# cpu_board.net
KiCad netlist of a schematic drawn in Altium Designer
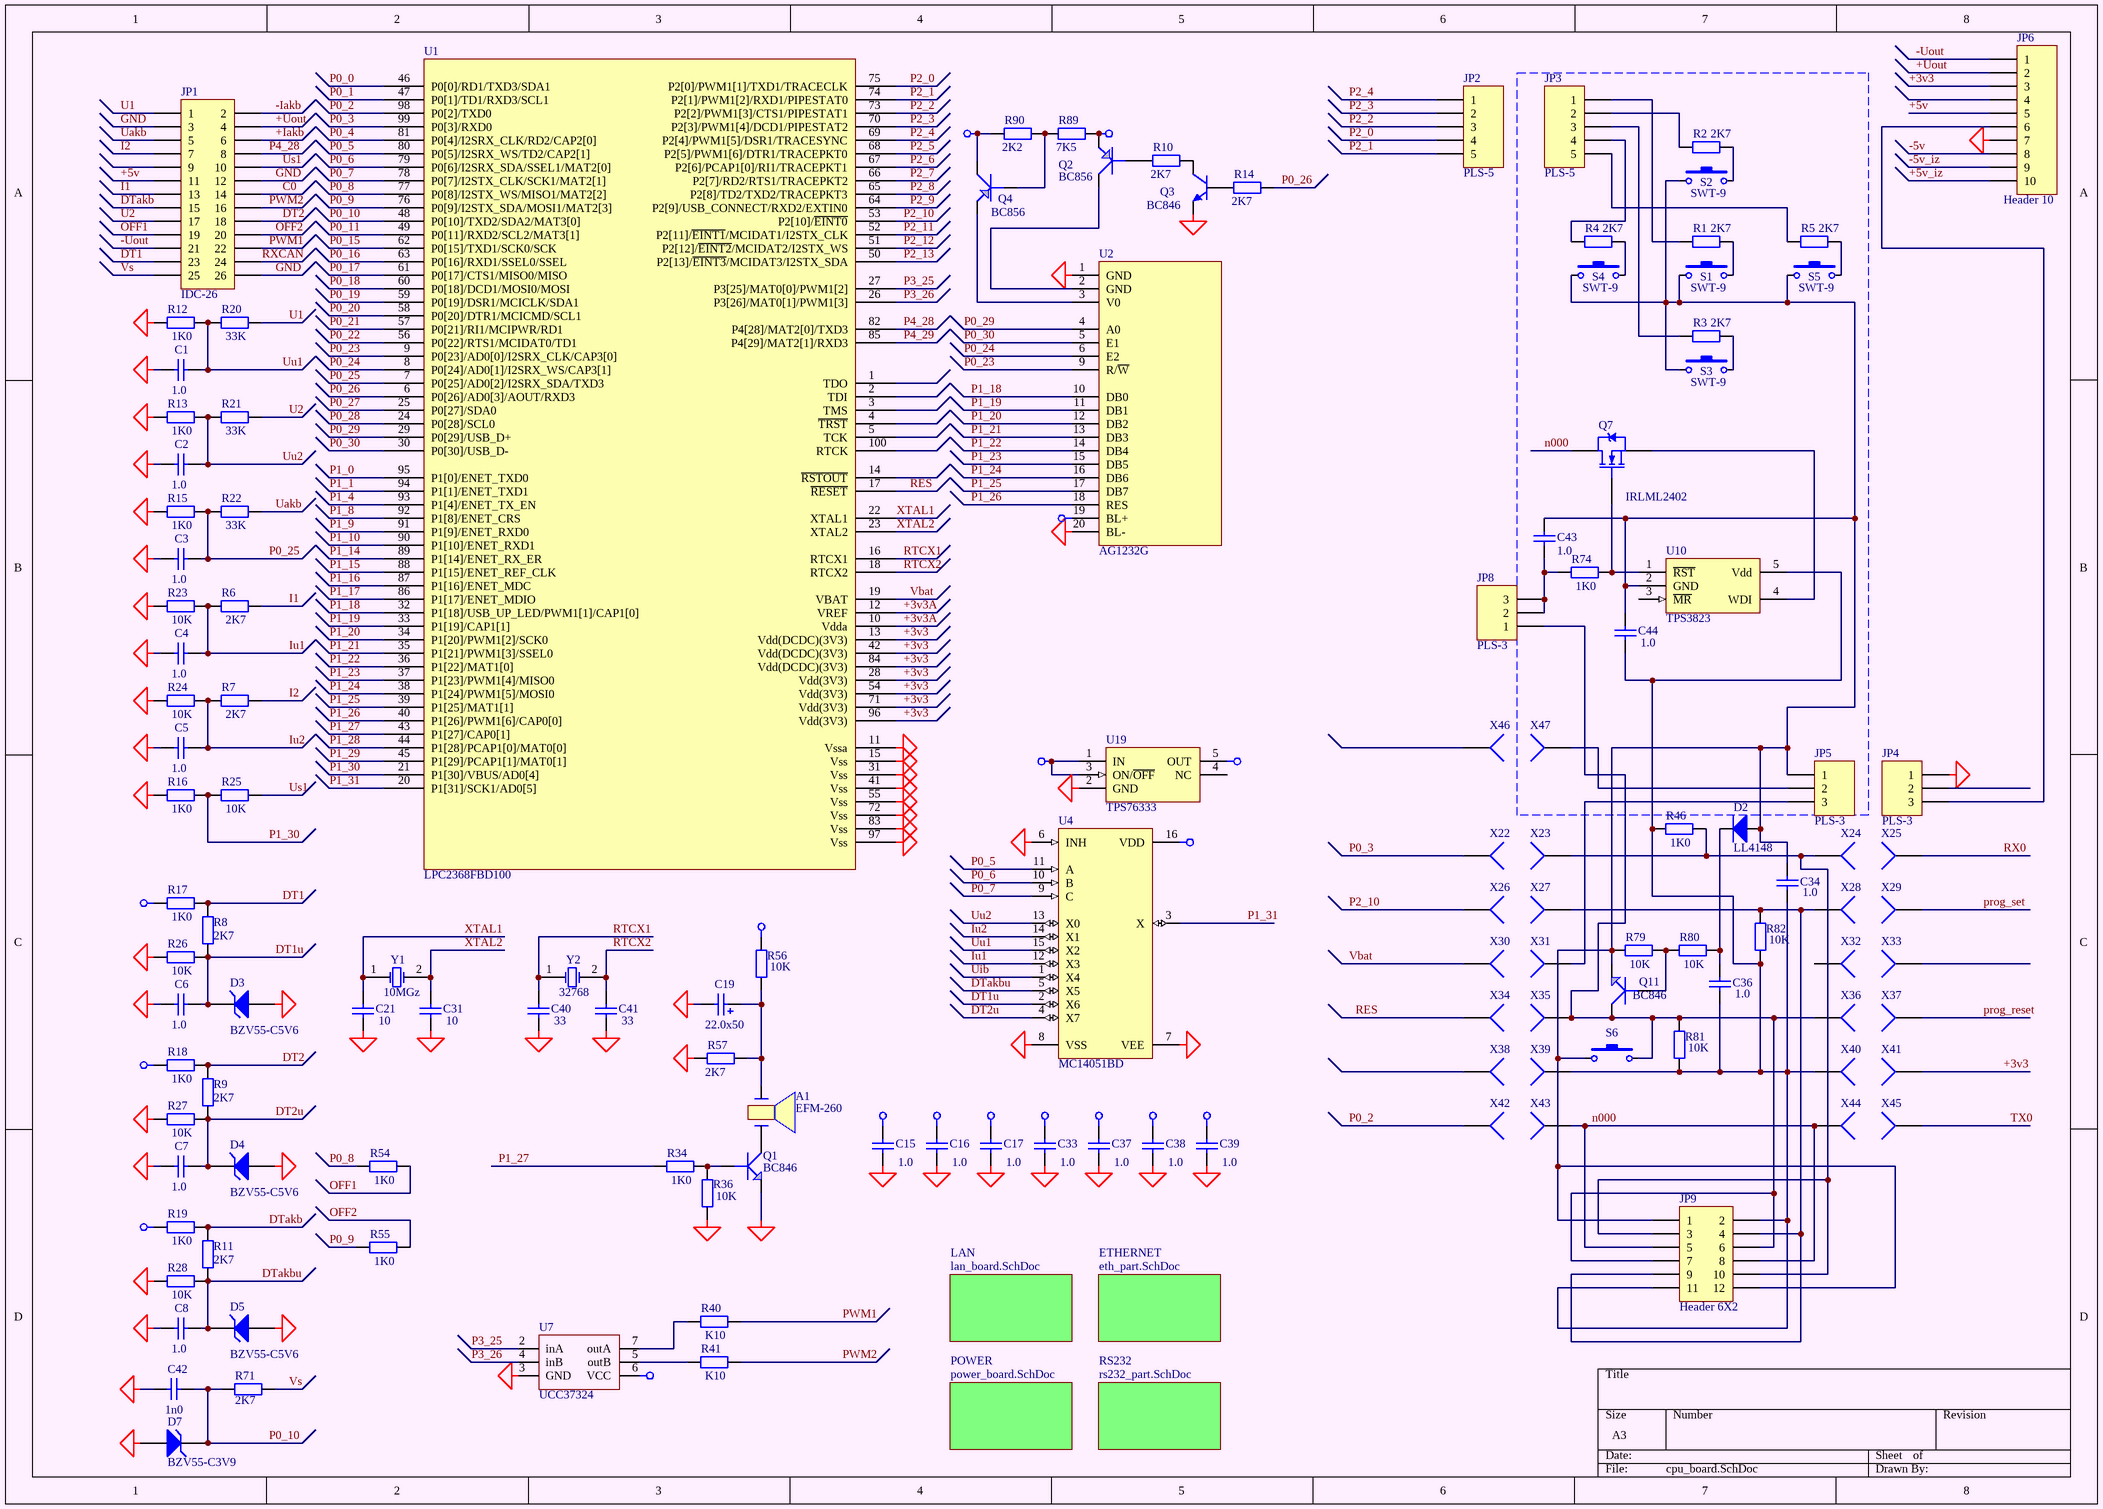
[diagram p0: cpu_board.SchDoc]

(export (version "E")
  (design (tool "Eeschema 10.0.6"))
  (components
    (comp (ref "A1") (value "EFM-260") (footprint "Pjezo15") (libsource (lib "PAL") (part "PJEZ0")))
    (comp (ref "C1")
      (value "1.0")
      (footprint "C3216-1206")
      (description "Capacitor (Semiconductor SIM Model)")
      (fields (field (name "MANUFACTURER") "Generic Components") (field (name "PUBLISHER") "Altium Limited"))
      (libsource (lib "Miscellaneous Devices") (part "Cap Semi"))
    )
    (comp (ref "C2")
      (value "1.0")
      (footprint "C3216-1206")
      (description "Capacitor (Semiconductor SIM Model)")
      (fields (field (name "MANUFACTURER") "Generic Components") (field (name "PUBLISHER") "Altium Limited"))
      (libsource (lib "Miscellaneous Devices") (part "Cap Semi"))
    )
    (comp (ref "C3")
      (value "1.0")
      (footprint "C3216-1206")
      (description "Capacitor (Semiconductor SIM Model)")
      (fields (field (name "MANUFACTURER") "Generic Components") (field (name "PUBLISHER") "Altium Limited"))
      (libsource (lib "Miscellaneous Devices") (part "Cap Semi"))
    )
    (comp (ref "C4")
      (value "1.0")
      (footprint "C3216-1206")
      (description "Capacitor (Semiconductor SIM Model)")
      (fields (field (name "MANUFACTURER") "Generic Components") (field (name "PUBLISHER") "Altium Limited"))
      (libsource (lib "Miscellaneous Devices") (part "Cap Semi"))
    )
    (comp (ref "C5")
      (value "1.0")
      (footprint "C3216-1206")
      (description "Capacitor (Semiconductor SIM Model)")
      (fields (field (name "MANUFACTURER") "Generic Components") (field (name "PUBLISHER") "Altium Limited"))
      (libsource (lib "Miscellaneous Devices") (part "Cap Semi"))
    )
    (comp (ref "C6")
      (value "1.0")
      (footprint "C3216-1206")
      (description "Capacitor (Semiconductor SIM Model)")
      (fields (field (name "MANUFACTURER") "Generic Components") (field (name "PUBLISHER") "Altium Limited"))
      (libsource (lib "Miscellaneous Devices") (part "Cap Semi"))
    )
    (comp (ref "C7")
      (value "1.0")
      (footprint "C3216-1206")
      (description "Capacitor (Semiconductor SIM Model)")
      (fields (field (name "MANUFACTURER") "Generic Components") (field (name "PUBLISHER") "Altium Limited"))
      (libsource (lib "Miscellaneous Devices") (part "Cap Semi"))
    )
    (comp (ref "C8")
      (value "1.0")
      (footprint "_1206")
      (description "Capacitor (Semiconductor SIM Model)")
      (fields (field (name "MANUFACTURER") "Generic Components") (field (name "PUBLISHER") "Altium Limited"))
      (libsource (lib "Miscellaneous Devices") (part "Cap Semi"))
    )
    (comp (ref "C15")
      (value "1.0")
      (footprint "C3216-1206")
      (description "Capacitor (Semiconductor SIM Model)")
      (fields (field (name "MANUFACTURER") "Generic Components") (field (name "PUBLISHER") "Altium Limited"))
      (libsource (lib "Miscellaneous Devices") (part "Cap Semi"))
    )
    (comp (ref "C16")
      (value "1.0")
      (footprint "C3216-1206")
      (description "Capacitor (Semiconductor SIM Model)")
      (fields (field (name "MANUFACTURER") "Generic Components") (field (name "PUBLISHER") "Altium Limited"))
      (libsource (lib "Miscellaneous Devices") (part "Cap Semi"))
    )
    (comp (ref "C17")
      (value "1.0")
      (footprint "_1206")
      (description "Capacitor (Semiconductor SIM Model)")
      (fields (field (name "MANUFACTURER") "Generic Components") (field (name "PUBLISHER") "Altium Limited"))
      (libsource (lib "Miscellaneous Devices") (part "Cap Semi"))
    )
    (comp (ref "C19")
      (value "22.0x50")
      (footprint "el3")
      (description "Polarized Capacitor (Radial)")
      (fields (field (name "MANUFACTURER") "Generic Components") (field (name "PUBLISHER") "Altium Limited"))
      (libsource (lib "PAL") (part "Cap Pol1"))
    )
    (comp (ref "C21")
      (value "10")
      (footprint "_1206")
      (description "Capacitor (Semiconductor SIM Model)")
      (fields (field (name "MANUFACTURER") "Generic Components") (field (name "PUBLISHER") "Altium Limited"))
      (libsource (lib "Miscellaneous Devices") (part "Cap Semi"))
    )
    (comp (ref "C31")
      (value "10")
      (footprint "_1206")
      (description "Capacitor (Semiconductor SIM Model)")
      (fields (field (name "MANUFACTURER") "Generic Components") (field (name "PUBLISHER") "Altium Limited"))
      (libsource (lib "Miscellaneous Devices") (part "Cap Semi"))
    )
    (comp (ref "C33")
      (value "1.0")
      (footprint "_1206")
      (description "Capacitor (Semiconductor SIM Model)")
      (fields (field (name "MANUFACTURER") "Generic Components") (field (name "PUBLISHER") "Altium Limited"))
      (libsource (lib "Miscellaneous Devices") (part "Cap Semi"))
    )
    (comp (ref "C34")
      (value "1.0")
      (footprint "C3216-1206")
      (description "Capacitor (Semiconductor SIM Model)")
      (fields (field (name "MANUFACTURER") "Generic Components") (field (name "PUBLISHER") "Altium Limited"))
      (libsource (lib "Miscellaneous Devices") (part "Cap Semi"))
    )
    (comp (ref "C36")
      (value "1.0")
      (footprint "C3216-1206")
      (description "Capacitor (Semiconductor SIM Model)")
      (fields (field (name "MANUFACTURER") "Generic Components") (field (name "PUBLISHER") "Altium Limited"))
      (libsource (lib "Miscellaneous Devices") (part "Cap Semi"))
    )
    (comp (ref "C37")
      (value "1.0")
      (footprint "_1206")
      (description "Capacitor (Semiconductor SIM Model)")
      (fields (field (name "MANUFACTURER") "Generic Components") (field (name "PUBLISHER") "Altium Limited"))
      (libsource (lib "Miscellaneous Devices") (part "Cap Semi"))
    )
    (comp (ref "C38")
      (value "1.0")
      (footprint "_1206")
      (description "Capacitor (Semiconductor SIM Model)")
      (fields (field (name "MANUFACTURER") "Generic Components") (field (name "PUBLISHER") "Altium Limited"))
      (libsource (lib "Miscellaneous Devices") (part "Cap Semi"))
    )
    (comp (ref "C39")
      (value "1.0")
      (footprint "_1206")
      (description "Capacitor (Semiconductor SIM Model)")
      (fields (field (name "MANUFACTURER") "Generic Components") (field (name "PUBLISHER") "Altium Limited"))
      (libsource (lib "Miscellaneous Devices") (part "Cap Semi"))
    )
    (comp (ref "C40")
      (value "33")
      (footprint "_1206")
      (description "Capacitor (Semiconductor SIM Model)")
      (fields (field (name "MANUFACTURER") "Generic Components") (field (name "PUBLISHER") "Altium Limited"))
      (libsource (lib "Miscellaneous Devices") (part "Cap Semi"))
    )
    (comp (ref "C41")
      (value "33")
      (footprint "_1206")
      (description "Capacitor (Semiconductor SIM Model)")
      (fields (field (name "MANUFACTURER") "Generic Components") (field (name "PUBLISHER") "Altium Limited"))
      (libsource (lib "Miscellaneous Devices") (part "Cap Semi"))
    )
    (comp (ref "C42")
      (value "1n0")
      (footprint "_1206")
      (description "Capacitor (Semiconductor SIM Model)")
      (fields (field (name "MANUFACTURER") "Generic Components") (field (name "PUBLISHER") "Altium Limited"))
      (libsource (lib "Miscellaneous Devices") (part "Cap Semi"))
    )
    (comp (ref "C43")
      (value "1.0")
      (footprint "_1206")
      (description "Capacitor")
      (fields (field (name "MANUFACTURER") "Generic Components") (field (name "PUBLISHER") "Altium Limited"))
      (libsource (lib "Miscellaneous Devices") (part "Cap Semi"))
    )
    (comp (ref "C44")
      (value "1.0")
      (footprint "_1206")
      (description "Capacitor")
      (fields (field (name "MANUFACTURER") "Generic Components") (field (name "PUBLISHER") "Altium Limited"))
      (libsource (lib "Miscellaneous Devices") (part "Cap Semi"))
    )
    (comp (ref "D2")
      (value "LL4148")
      (footprint "_1206d")
      (description "Default Diode")
      (fields (field (name "MANUFACTURER") "Generic Components") (field (name "PUBLISHER") "Altium Limited"))
      (libsource (lib "PAL") (part "Diode"))
    )
    (comp (ref "D3")
      (value "BZV55-C5V6")
      (footprint "_1206d")
      (description "Zener Diode")
      (fields (field (name "MANUFACTURER") "Generic Components") (field (name "PUBLISHER") "Altium Limited"))
      (libsource (lib "Miscellaneous Devices") (part "D Zener"))
    )
    (comp (ref "D4")
      (value "BZV55-C5V6")
      (footprint "_1206d")
      (description "Zener Diode")
      (fields (field (name "MANUFACTURER") "Generic Components") (field (name "PUBLISHER") "Altium Limited"))
      (libsource (lib "Miscellaneous Devices") (part "D Zener"))
    )
    (comp (ref "D5")
      (value "BZV55-C5V6")
      (footprint "_1206d")
      (description "Zener Diode")
      (fields (field (name "MANUFACTURER") "Generic Components") (field (name "PUBLISHER") "Altium Limited"))
      (libsource (lib "Miscellaneous Devices") (part "D Zener"))
    )
    (comp (ref "D7")
      (value "BZV55-C3V9")
      (footprint "_1206d")
      (description "Zener Diode")
      (fields (field (name "MANUFACTURER") "Generic Components") (field (name "PUBLISHER") "Altium Limited"))
      (libsource (lib "Miscellaneous Devices") (part "D Zener"))
    )
    (comp (ref "JP1")
      (value "IDC-26")
      (footprint "SCM-26")
      (description "Header, 13-Pin, Dual row")
      (fields (field (name "MANUFACTURER") "Generic Components") (field (name "PUBLISHER") "Altium Limited"))
      (libsource (lib "Miscellaneous Connectors") (part "MHDR2X13"))
    )
    (comp (ref "JP2")
      (value "PLS-5")
      (footprint "HDR1X5")
      (description "Header, 5-Pin")
      (fields (field (name "MANUFACTURER") "Generic Components") (field (name "PUBLISHER") "Altium Limited"))
      (libsource (lib "Miscellaneous Connectors") (part "Header 5"))
    )
    (comp (ref "JP3")
      (value "PLS-5")
      (footprint "HDR1X5")
      (description "Header, 5-Pin")
      (fields (field (name "MANUFACTURER") "Generic Components") (field (name "PUBLISHER") "Altium Limited"))
      (libsource (lib "") (part "Header 5_1"))
    )
    (comp (ref "JP4")
      (value "PLS-3")
      (footprint "HDR1X3")
      (description "Header, 3-Pin")
      (fields (field (name "MANUFACTURER") "Generic Components") (field (name "PUBLISHER") "Altium Limited"))
      (libsource (lib "Miscellaneous Connectors") (part "Header 3"))
    )
    (comp (ref "JP5")
      (value "PLS-3")
      (footprint "HDR1X3")
      (description "Header, 3-Pin")
      (fields (field (name "MANUFACTURER") "Generic Components") (field (name "PUBLISHER") "Altium Limited"))
      (libsource (lib "") (part "Header 3_2"))
    )
    (comp (ref "JP6")
      (value "Header 10")
      (footprint "HDR2X5")
      (description "Header, 10-Pin")
      (fields (field (name "MANUFACTURER") "Generic Components") (field (name "PUBLISHER") "Altium Limited"))
      (libsource (lib "Miscellaneous Connectors") (part "Header 10"))
    )
    (comp (ref "JP8")
      (value "PLS-3")
      (footprint "HDR1X3")
      (description "Header, 3-Pin")
      (fields (field (name "MANUFACTURER") "Generic Components") (field (name "PUBLISHER") "Altium Limited"))
      (libsource (lib "") (part "Header 3_1"))
    )
    (comp (ref "JP9")
      (value "Header 6X2")
      (footprint "sl-12mini")
      (description "Header, 6-Pin, Dual row")
      (fields (field (name "MANUFACTURER") "Generic Components") (field (name "PUBLISHER") "Altium Limited"))
      (libsource (lib "Miscellaneous Connectors") (part "Header 6X2"))
    )
    (comp (ref "Q1") (value "BC846") (footprint "SOT 23:SO-G3") (libsource (lib "MAIN") (part "GT122")))
    (comp (ref "Q2") (value "BC856") (footprint "SO-G3") (libsource (lib "MAIN") (part "GT109")))
    (comp (ref "Q3")
      (value "BC846")
      (footprint "SO-G3")
      (description "General Purpose Transistor NPN Silicon")
      (fields (field (name "MANUFACTURER") "Motorola") (field (name "PUBLISHER") "Altium Limited"))
      (libsource (lib "PAL") (part "BC847ALT1"))
    )
    (comp (ref "Q4") (value "BC856") (footprint "SO-G3") (libsource (lib "MAIN") (part "GT109")))
    (comp (ref "Q7")
      (value "IRLML2402")
      (footprint "SO-G3")
      (description "HEXFET Power MOSFET")
      (fields
        (field (name "MANUFACTURER") "International Rectifier")
        (field (name "ALTIUM_VALUE") "IRLML2402")
        (field (name "PUBLISHER") "Altium Limited")
      )
      (libsource (lib "IR Discrete MOSFET") (part "IRLML2402"))
    )
    (comp (ref "Q11") (value "BC846") (footprint "SOT 23:SO-G3") (libsource (lib "MAIN") (part "GT122")))
    (comp (ref "R1")
      (value "2K7")
      (footprint "_1206")
      (description "Resistor")
      (fields (field (name "MANUFACTURER") "Generic Components") (field (name "PUBLISHER") "Altium Limited"))
      (libsource (lib "Miscellaneous Devices") (part "Res2"))
    )
    (comp (ref "R2")
      (value "2K7")
      (footprint "_1206")
      (description "Resistor")
      (fields (field (name "MANUFACTURER") "Generic Components") (field (name "PUBLISHER") "Altium Limited"))
      (libsource (lib "Miscellaneous Devices") (part "Res2"))
    )
    (comp (ref "R3")
      (value "2K7")
      (footprint "_1206")
      (description "Resistor")
      (fields (field (name "MANUFACTURER") "Generic Components") (field (name "PUBLISHER") "Altium Limited"))
      (libsource (lib "Miscellaneous Devices") (part "Res2"))
    )
    (comp (ref "R4")
      (value "2K7")
      (footprint "_1206")
      (description "Resistor")
      (fields (field (name "MANUFACTURER") "Generic Components") (field (name "PUBLISHER") "Altium Limited"))
      (libsource (lib "Miscellaneous Devices") (part "Res2"))
    )
    (comp (ref "R5")
      (value "2K7")
      (footprint "_1206")
      (description "Resistor")
      (fields (field (name "MANUFACTURER") "Generic Components") (field (name "PUBLISHER") "Altium Limited"))
      (libsource (lib "Miscellaneous Devices") (part "Res2"))
    )
    (comp (ref "R6")
      (value "2K7")
      (footprint "_1206")
      (description "Resistor")
      (fields (field (name "MANUFACTURER") "Generic Components") (field (name "PUBLISHER") "Altium Limited"))
      (libsource (lib "") (part "Res2_2"))
    )
    (comp (ref "R7")
      (value "2K7")
      (footprint "_1206")
      (description "Resistor")
      (fields (field (name "MANUFACTURER") "Generic Components") (field (name "PUBLISHER") "Altium Limited"))
      (libsource (lib "") (part "Res2_2"))
    )
    (comp (ref "R8")
      (value "2K7")
      (footprint "_1206")
      (description "Resistor")
      (fields (field (name "MANUFACTURER") "Generic Components") (field (name "PUBLISHER") "Altium Limited"))
      (libsource (lib "") (part "Res2_3"))
    )
    (comp (ref "R9")
      (value "2K7")
      (footprint "_1206")
      (description "Resistor")
      (fields (field (name "MANUFACTURER") "Generic Components") (field (name "PUBLISHER") "Altium Limited"))
      (libsource (lib "") (part "Res2_3"))
    )
    (comp (ref "R10")
      (value "2K7")
      (footprint "_1206")
      (description "Resistor")
      (fields (field (name "MANUFACTURER") "Generic Components") (field (name "PUBLISHER") "Altium Limited"))
      (libsource (lib "") (part "Res2_1"))
    )
    (comp (ref "R11")
      (value "2K7")
      (footprint "_1206")
      (description "Resistor")
      (fields (field (name "MANUFACTURER") "Generic Components") (field (name "PUBLISHER") "Altium Limited"))
      (libsource (lib "") (part "Res2_3"))
    )
    (comp (ref "R12")
      (value "1K0")
      (footprint "_1206")
      (description "Resistor")
      (fields (field (name "MANUFACTURER") "Generic Components") (field (name "PUBLISHER") "Altium Limited"))
      (libsource (lib "") (part "Res2_1"))
    )
    (comp (ref "R13")
      (value "1K0")
      (footprint "_1206")
      (description "Resistor")
      (fields (field (name "MANUFACTURER") "Generic Components") (field (name "PUBLISHER") "Altium Limited"))
      (libsource (lib "") (part "Res2_1"))
    )
    (comp (ref "R14")
      (value "2K7")
      (footprint "_1206")
      (description "Resistor")
      (fields (field (name "MANUFACTURER") "Generic Components") (field (name "PUBLISHER") "Altium Limited"))
      (libsource (lib "") (part "Res2_1"))
    )
    (comp (ref "R15")
      (value "1K0")
      (footprint "_1206")
      (description "Resistor")
      (fields (field (name "MANUFACTURER") "Generic Components") (field (name "PUBLISHER") "Altium Limited"))
      (libsource (lib "") (part "Res2_1"))
    )
    (comp (ref "R16")
      (value "1K0")
      (footprint "_1206")
      (description "Resistor")
      (fields (field (name "MANUFACTURER") "Generic Components") (field (name "PUBLISHER") "Altium Limited"))
      (libsource (lib "") (part "Res2_1"))
    )
    (comp (ref "R17")
      (value "1K0")
      (footprint "_1206")
      (description "Resistor")
      (fields (field (name "MANUFACTURER") "Generic Components") (field (name "PUBLISHER") "Altium Limited"))
      (libsource (lib "") (part "Res2_1"))
    )
    (comp (ref "R18")
      (value "1K0")
      (footprint "_1206")
      (description "Resistor")
      (fields (field (name "MANUFACTURER") "Generic Components") (field (name "PUBLISHER") "Altium Limited"))
      (libsource (lib "") (part "Res2_1"))
    )
    (comp (ref "R19")
      (value "1K0")
      (footprint "_1206")
      (description "Resistor")
      (fields (field (name "MANUFACTURER") "Generic Components") (field (name "PUBLISHER") "Altium Limited"))
      (libsource (lib "") (part "Res2_1"))
    )
    (comp (ref "R20")
      (value "33K")
      (footprint "_1206")
      (description "Resistor")
      (fields (field (name "MANUFACTURER") "Generic Components") (field (name "PUBLISHER") "Altium Limited"))
      (libsource (lib "") (part "Res2_2"))
    )
    (comp (ref "R21")
      (value "33K")
      (footprint "_1206")
      (description "Resistor")
      (fields (field (name "MANUFACTURER") "Generic Components") (field (name "PUBLISHER") "Altium Limited"))
      (libsource (lib "") (part "Res2_2"))
    )
    (comp (ref "R22")
      (value "33K")
      (footprint "_1206")
      (description "Resistor")
      (fields (field (name "MANUFACTURER") "Generic Components") (field (name "PUBLISHER") "Altium Limited"))
      (libsource (lib "") (part "Res2_2"))
    )
    (comp (ref "R23")
      (value "10K")
      (footprint "_1206")
      (description "Resistor")
      (fields (field (name "MANUFACTURER") "Generic Components") (field (name "PUBLISHER") "Altium Limited"))
      (libsource (lib "") (part "Res2_2"))
    )
    (comp (ref "R24")
      (value "10K")
      (footprint "_1206")
      (description "Resistor")
      (fields (field (name "MANUFACTURER") "Generic Components") (field (name "PUBLISHER") "Altium Limited"))
      (libsource (lib "") (part "Res2_2"))
    )
    (comp (ref "R25")
      (value "10K")
      (footprint "_1206")
      (description "Resistor")
      (fields (field (name "MANUFACTURER") "Generic Components") (field (name "PUBLISHER") "Altium Limited"))
      (libsource (lib "") (part "Res2_2"))
    )
    (comp (ref "R26")
      (value "10K")
      (footprint "_1206")
      (description "Resistor")
      (fields (field (name "MANUFACTURER") "Generic Components") (field (name "PUBLISHER") "Altium Limited"))
      (libsource (lib "") (part "Res2_2"))
    )
    (comp (ref "R27")
      (value "10K")
      (footprint "_1206")
      (description "Resistor")
      (fields (field (name "MANUFACTURER") "Generic Components") (field (name "PUBLISHER") "Altium Limited"))
      (libsource (lib "") (part "Res2_2"))
    )
    (comp (ref "R28")
      (value "10K")
      (footprint "_1206")
      (description "Resistor")
      (fields (field (name "MANUFACTURER") "Generic Components") (field (name "PUBLISHER") "Altium Limited"))
      (libsource (lib "") (part "Res2_2"))
    )
    (comp (ref "R34")
      (value "1K0")
      (footprint "_1206")
      (description "Resistor")
      (fields (field (name "MANUFACTURER") "Generic Components") (field (name "PUBLISHER") "Altium Limited"))
      (libsource (lib "") (part "Res2_2"))
    )
    (comp (ref "R36")
      (value "10K")
      (footprint "_1206")
      (description "Resistor")
      (fields (field (name "MANUFACTURER") "Generic Components") (field (name "PUBLISHER") "Altium Limited"))
      (libsource (lib "") (part "Res2_3"))
    )
    (comp (ref "R40")
      (value "K10")
      (footprint "_1206")
      (description "Resistor")
      (fields (field (name "MANUFACTURER") "Generic Components") (field (name "PUBLISHER") "Altium Limited"))
      (libsource (lib "") (part "Res2_1"))
    )
    (comp (ref "R41")
      (value "K10")
      (footprint "_1206")
      (description "Resistor")
      (fields (field (name "MANUFACTURER") "Generic Components") (field (name "PUBLISHER") "Altium Limited"))
      (libsource (lib "") (part "Res2_1"))
    )
    (comp (ref "R46")
      (value "1K0")
      (footprint "_1206")
      (description "Resistor")
      (fields (field (name "MANUFACTURER") "Generic Components") (field (name "PUBLISHER") "Altium Limited"))
      (libsource (lib "") (part "Res2_1"))
    )
    (comp (ref "R54")
      (value "1K0")
      (footprint "_1206")
      (description "Resistor")
      (fields (field (name "MANUFACTURER") "Generic Components") (field (name "PUBLISHER") "Altium Limited"))
      (libsource (lib "") (part "Res2_2"))
    )
    (comp (ref "R55")
      (value "1K0")
      (footprint "_1206")
      (description "Resistor")
      (fields (field (name "MANUFACTURER") "Generic Components") (field (name "PUBLISHER") "Altium Limited"))
      (libsource (lib "") (part "Res2_2"))
    )
    (comp (ref "R56")
      (value "10K")
      (footprint "_1206")
      (description "Resistor")
      (fields (field (name "MANUFACTURER") "Generic Components") (field (name "PUBLISHER") "Altium Limited"))
      (libsource (lib "") (part "Res2_3"))
    )
    (comp (ref "R57")
      (value "2K7")
      (footprint "_1206")
      (description "Resistor")
      (fields (field (name "MANUFACTURER") "Generic Components") (field (name "PUBLISHER") "Altium Limited"))
      (libsource (lib "") (part "Res2_2"))
    )
    (comp (ref "R71")
      (value "2K7")
      (footprint "_1206")
      (description "Resistor")
      (fields (field (name "MANUFACTURER") "Generic Components") (field (name "PUBLISHER") "Altium Limited"))
      (libsource (lib "") (part "Res2_1"))
    )
    (comp (ref "R74")
      (value "1K0")
      (footprint "_1206")
      (description "Resistor")
      (fields (field (name "MANUFACTURER") "Generic Components") (field (name "PUBLISHER") "Altium Limited"))
      (libsource (lib "") (part "Res2_1"))
    )
    (comp (ref "R79")
      (value "10K")
      (footprint "_1206")
      (description "Resistor")
      (fields (field (name "MANUFACTURER") "Generic Components") (field (name "PUBLISHER") "Altium Limited"))
      (libsource (lib "") (part "Res2_2"))
    )
    (comp (ref "R80")
      (value "10K")
      (footprint "_1206")
      (description "Resistor")
      (fields (field (name "MANUFACTURER") "Generic Components") (field (name "PUBLISHER") "Altium Limited"))
      (libsource (lib "") (part "Res2_2"))
    )
    (comp (ref "R81")
      (value "10K")
      (footprint "_1206")
      (description "Resistor")
      (fields (field (name "MANUFACTURER") "Generic Components") (field (name "PUBLISHER") "Altium Limited"))
      (libsource (lib "") (part "Res2_3"))
    )
    (comp (ref "R82")
      (value "10K")
      (footprint "_1206")
      (description "Resistor")
      (fields (field (name "MANUFACTURER") "Generic Components") (field (name "PUBLISHER") "Altium Limited"))
      (libsource (lib "") (part "Res2_3"))
    )
    (comp (ref "R89")
      (value "7K5")
      (footprint "_1206")
      (description "Resistor")
      (fields (field (name "MANUFACTURER") "Generic Components") (field (name "PUBLISHER") "Altium Limited"))
      (libsource (lib "") (part "Res2_2"))
    )
    (comp (ref "R90")
      (value "2K2")
      (footprint "_1206")
      (description "Resistor")
      (fields (field (name "MANUFACTURER") "Generic Components") (field (name "PUBLISHER") "Altium Limited"))
      (libsource (lib "") (part "Res2_2"))
    )
    (comp (ref "S1")
      (value "SWT-9")
      (footprint "SWT-9")
      (description "Switch")
      (fields (field (name "MANUFACTURER") "Generic Components") (field (name "PUBLISHER") "Altium Limited"))
      (libsource (lib "PAL") (part "SWT-9"))
    )
    (comp (ref "S2")
      (value "SWT-9")
      (footprint "SWT-9")
      (description "Switch")
      (fields (field (name "MANUFACTURER") "Generic Components") (field (name "PUBLISHER") "Altium Limited"))
      (libsource (lib "PAL") (part "SWT-9"))
    )
    (comp (ref "S3")
      (value "SWT-9")
      (footprint "SWT-9")
      (description "Switch")
      (fields (field (name "MANUFACTURER") "Generic Components") (field (name "PUBLISHER") "Altium Limited"))
      (libsource (lib "PAL") (part "SWT-9"))
    )
    (comp (ref "S4")
      (value "SWT-9")
      (footprint "SWT-9")
      (description "Switch")
      (fields (field (name "MANUFACTURER") "Generic Components") (field (name "PUBLISHER") "Altium Limited"))
      (libsource (lib "PAL") (part "SWT-9"))
    )
    (comp (ref "S5")
      (value "SWT-9")
      (footprint "SWT-9")
      (description "Switch")
      (fields (field (name "MANUFACTURER") "Generic Components") (field (name "PUBLISHER") "Altium Limited"))
      (libsource (lib "PAL") (part "SWT-9"))
    )
    (comp (ref "S6")
      (value "SWT-6")
      (footprint "SWT-6")
      (description "Button")
      (fields (field (name "MANUFACTURER") "Generic Components") (field (name "PUBLISHER") "Altium Limited"))
      (libsource (lib "PAL") (part "SWT-9"))
    )
    (comp (ref "U1")
      (value "LPC2368FBD100")
      (footprint "LPC2368")
      (libsource (lib "PAL") (part "LPC2368FBD100"))
    )
    (comp (ref "U2") (value "AG1232G") (footprint "AG1232G") (libsource (lib "PAL") (part "AG1232G")))
    (comp (ref "U4")
      (value "MC14051BD")
      (footprint "SO-G16/C5.85")
      (description "8-Channel Analog Multiplexer/Demultiplexer")
      (fields (field (name "MANUFACTURER") "ON Semiconductor") (field (name "PUBLISHER") "Altium Limited"))
      (libsource (lib "ON Semi Logic Multiplexer") (part "MC14051BD"))
    )
    (comp (ref "U7") (value "UCC37324") (footprint "SO-G8") (libsource (lib "PAL") (part "UCC37324")))
    (comp (ref "U10")
      (value "TPS3823")
      (footprint "SO-G5/P.95")
      (description "Reset IC")
      (fields
        (field (name "MANUFACTURER") "National Semiconductor")
        (field (name "PUBLISHER") "Altium Limited")
      )
      (libsource (lib "PAL") (part "TPS3823"))
    )
    (comp (ref "U19")
      (value "TPS76333")
      (footprint "SO-G5/P.95")
      (description "Micropower SOT, 50 mA Ultra Low-Dropout Regulator")
      (fields
        (field (name "MANUFACTURER") "National Semiconductor")
        (field (name "PUBLISHER") "Altium Limited")
      )
      (libsource (lib "NSC Power Mgt Voltage Regulator") (part "LP2980AIM5-3.3"))
    )
    (comp (ref "X22")
      (value "~")
      (footprint "PIN1")
      (description "Socket")
      (fields (field (name "MANUFACTURER") "Generic Components") (field (name "PUBLISHER") "Altium Limited"))
      (libsource (lib "Miscellaneous Connectors") (part "Socket"))
    )
    (comp (ref "X23")
      (value "~")
      (footprint "PIN1")
      (description "Socket")
      (fields (field (name "MANUFACTURER") "Generic Components") (field (name "PUBLISHER") "Altium Limited"))
      (libsource (lib "Miscellaneous Connectors") (part "Socket"))
    )
    (comp (ref "X24")
      (value "~")
      (footprint "PIN1")
      (description "Socket")
      (fields (field (name "MANUFACTURER") "Generic Components") (field (name "PUBLISHER") "Altium Limited"))
      (libsource (lib "Miscellaneous Connectors") (part "Socket"))
    )
    (comp (ref "X25")
      (value "~")
      (footprint "PIN1")
      (description "Socket")
      (fields (field (name "MANUFACTURER") "Generic Components") (field (name "PUBLISHER") "Altium Limited"))
      (libsource (lib "Miscellaneous Connectors") (part "Socket"))
    )
    (comp (ref "X26")
      (value "~")
      (footprint "PIN1")
      (description "Socket")
      (fields (field (name "MANUFACTURER") "Generic Components") (field (name "PUBLISHER") "Altium Limited"))
      (libsource (lib "Miscellaneous Connectors") (part "Socket"))
    )
    (comp (ref "X27")
      (value "~")
      (footprint "PIN1")
      (description "Socket")
      (fields (field (name "MANUFACTURER") "Generic Components") (field (name "PUBLISHER") "Altium Limited"))
      (libsource (lib "Miscellaneous Connectors") (part "Socket"))
    )
    (comp (ref "X28")
      (value "~")
      (footprint "PIN1")
      (description "Socket")
      (fields (field (name "MANUFACTURER") "Generic Components") (field (name "PUBLISHER") "Altium Limited"))
      (libsource (lib "Miscellaneous Connectors") (part "Socket"))
    )
    (comp (ref "X29")
      (value "~")
      (footprint "PIN1")
      (description "Socket")
      (fields (field (name "MANUFACTURER") "Generic Components") (field (name "PUBLISHER") "Altium Limited"))
      (libsource (lib "Miscellaneous Connectors") (part "Socket"))
    )
    (comp (ref "X30")
      (value "~")
      (footprint "PIN1")
      (description "Socket")
      (fields (field (name "MANUFACTURER") "Generic Components") (field (name "PUBLISHER") "Altium Limited"))
      (libsource (lib "Miscellaneous Connectors") (part "Socket"))
    )
    (comp (ref "X31")
      (value "~")
      (footprint "PIN1")
      (description "Socket")
      (fields (field (name "MANUFACTURER") "Generic Components") (field (name "PUBLISHER") "Altium Limited"))
      (libsource (lib "Miscellaneous Connectors") (part "Socket"))
    )
    (comp (ref "X32")
      (value "~")
      (footprint "PIN1")
      (description "Socket")
      (fields (field (name "MANUFACTURER") "Generic Components") (field (name "PUBLISHER") "Altium Limited"))
      (libsource (lib "Miscellaneous Connectors") (part "Socket"))
    )
    (comp (ref "X33")
      (value "~")
      (footprint "PIN1")
      (description "Socket")
      (fields (field (name "MANUFACTURER") "Generic Components") (field (name "PUBLISHER") "Altium Limited"))
      (libsource (lib "Miscellaneous Connectors") (part "Socket"))
    )
    (comp (ref "X34")
      (value "~")
      (footprint "PIN1")
      (description "Socket")
      (fields (field (name "MANUFACTURER") "Generic Components") (field (name "PUBLISHER") "Altium Limited"))
      (libsource (lib "Miscellaneous Connectors") (part "Socket"))
    )
    (comp (ref "X35")
      (value "~")
      (footprint "PIN1")
      (description "Socket")
      (fields (field (name "MANUFACTURER") "Generic Components") (field (name "PUBLISHER") "Altium Limited"))
      (libsource (lib "Miscellaneous Connectors") (part "Socket"))
    )
    (comp (ref "X36")
      (value "~")
      (footprint "PIN1")
      (description "Socket")
      (fields (field (name "MANUFACTURER") "Generic Components") (field (name "PUBLISHER") "Altium Limited"))
      (libsource (lib "Miscellaneous Connectors") (part "Socket"))
    )
    (comp (ref "X37")
      (value "~")
      (footprint "PIN1")
      (description "Socket")
      (fields (field (name "MANUFACTURER") "Generic Components") (field (name "PUBLISHER") "Altium Limited"))
      (libsource (lib "Miscellaneous Connectors") (part "Socket"))
    )
    (comp (ref "X38")
      (value "~")
      (footprint "PIN1")
      (description "Socket")
      (fields (field (name "MANUFACTURER") "Generic Components") (field (name "PUBLISHER") "Altium Limited"))
      (libsource (lib "Miscellaneous Connectors") (part "Socket"))
    )
    (comp (ref "X39")
      (value "~")
      (footprint "PIN1")
      (description "Socket")
      (fields (field (name "MANUFACTURER") "Generic Components") (field (name "PUBLISHER") "Altium Limited"))
      (libsource (lib "Miscellaneous Connectors") (part "Socket"))
    )
    (comp (ref "X40")
      (value "~")
      (footprint "PIN1")
      (description "Socket")
      (fields (field (name "MANUFACTURER") "Generic Components") (field (name "PUBLISHER") "Altium Limited"))
      (libsource (lib "Miscellaneous Connectors") (part "Socket"))
    )
    (comp (ref "X41")
      (value "~")
      (footprint "PIN1")
      (description "Socket")
      (fields (field (name "MANUFACTURER") "Generic Components") (field (name "PUBLISHER") "Altium Limited"))
      (libsource (lib "Miscellaneous Connectors") (part "Socket"))
    )
    (comp (ref "X42")
      (value "~")
      (footprint "PIN1")
      (description "Socket")
      (fields (field (name "MANUFACTURER") "Generic Components") (field (name "PUBLISHER") "Altium Limited"))
      (libsource (lib "Miscellaneous Connectors") (part "Socket"))
    )
    (comp (ref "X43")
      (value "~")
      (footprint "PIN1")
      (description "Socket")
      (fields (field (name "MANUFACTURER") "Generic Components") (field (name "PUBLISHER") "Altium Limited"))
      (libsource (lib "Miscellaneous Connectors") (part "Socket"))
    )
    (comp (ref "X44")
      (value "~")
      (footprint "PIN1")
      (description "Socket")
      (fields (field (name "MANUFACTURER") "Generic Components") (field (name "PUBLISHER") "Altium Limited"))
      (libsource (lib "Miscellaneous Connectors") (part "Socket"))
    )
    (comp (ref "X45")
      (value "~")
      (footprint "PIN1")
      (description "Socket")
      (fields (field (name "MANUFACTURER") "Generic Components") (field (name "PUBLISHER") "Altium Limited"))
      (libsource (lib "Miscellaneous Connectors") (part "Socket"))
    )
    (comp (ref "X46")
      (value "~")
      (footprint "PIN1")
      (description "Socket")
      (fields (field (name "MANUFACTURER") "Generic Components") (field (name "PUBLISHER") "Altium Limited"))
      (libsource (lib "Miscellaneous Connectors") (part "Socket"))
    )
    (comp (ref "X47")
      (value "~")
      (footprint "PIN1")
      (description "Socket")
      (fields (field (name "MANUFACTURER") "Generic Components") (field (name "PUBLISHER") "Altium Limited"))
      (libsource (lib "Miscellaneous Connectors") (part "Socket"))
    )
    (comp (ref "Y1")
      (value "10MGz")
      (footprint "QWARZ1")
      (description "Crystal Oscillator")
      (fields (field (name "MANUFACTURER") "Generic Components") (field (name "PUBLISHER") "Altium Limited"))
      (libsource (lib "Miscellaneous Devices") (part "XTAL"))
    )
    (comp (ref "Y2")
      (value "32768")
      (footprint "QWARZ2")
      (description "Crystal Oscillator")
      (fields (field (name "MANUFACTURER") "Generic Components") (field (name "PUBLISHER") "Altium Limited"))
      (libsource (lib "") (part "XTAL_1"))
    )
  )
  (nets
    (net (code "1") (name "+3v3") (class "Default")
      (node (ref "C37") (pin "2") (pinfunction "2_2") (pintype "passive"))
      (node (ref "C38") (pin "2") (pinfunction "2_2") (pintype "passive"))
      (node (ref "C39") (pin "2") (pinfunction "2_2") (pintype "passive"))
      (node (ref "JP6") (pin "3") (pinfunction "3_3") (pintype "passive"))
      (node (ref "U1") (pin "13") (pinfunction "Vdd(DCDC)(3V3)_13") (pintype "passive"))
      (node (ref "U1") (pin "28") (pinfunction "Vdd(3V3)_28") (pintype "passive"))
      (node (ref "U1") (pin "42") (pinfunction "Vdd(DCDC)(3V3)_42") (pintype "passive"))
      (node (ref "U1") (pin "54") (pinfunction "Vdd(3V3)_54") (pintype "passive"))
      (node (ref "U1") (pin "71") (pinfunction "Vdd(3V3)_71") (pintype "passive"))
      (node (ref "U1") (pin "84") (pinfunction "Vdd(DCDC)(3V3)_84") (pintype "passive"))
      (node (ref "U1") (pin "96") (pinfunction "Vdd(3V3)_96") (pintype "passive"))
      (node (ref "U4") (pin "16") (pinfunction "VDD_16") (pintype "power_in"))
      (node (ref "X41") (pin "1") (pinfunction "1_1") (pintype "passive"))
    )
    (net (code "2") (name "+3v3A") (class "Default")
      (node (ref "C17") (pin "2") (pinfunction "2_2") (pintype "passive"))
      (node (ref "C33") (pin "2") (pinfunction "2_2") (pintype "passive"))
      (node (ref "U1") (pin "10") (pinfunction "Vdda_10") (pintype "passive"))
      (node (ref "U1") (pin "12") (pinfunction "VREF_12") (pintype "passive"))
      (node (ref "U19") (pin "5") (pinfunction "OUT_5") (pintype "power_in"))
    )
    (net (code "3") (name "+5v") (class "Default")
      (node (ref "C15") (pin "2") (pinfunction "2_2") (pintype "passive"))
      (node (ref "JP1") (pin "11") (pinfunction "11_11") (pintype "passive"))
      (node (ref "JP6") (pin "5") (pinfunction "5_5") (pintype "passive"))
      (node (ref "Q2") (pin "2") (pinfunction "E_2") (pintype "passive"))
      (node (ref "R17") (pin "2") (pinfunction "2_2") (pintype "passive"))
      (node (ref "R18") (pin "2") (pinfunction "2_2") (pintype "passive"))
      (node (ref "R19") (pin "2") (pinfunction "2_2") (pintype "passive"))
      (node (ref "R89") (pin "2") (pinfunction "2_2") (pintype "passive"))
      (node (ref "U19") (pin "1") (pinfunction "IN_1") (pintype "power_in"))
      (node (ref "U19") (pin "3") (pinfunction "ON/~{OFF}_3") (pintype "input"))
      (node (ref "U2") (pin "19") (pinfunction "BL+_19") (pintype "passive"))
      (node (ref "U7") (pin "6") (pinfunction "VCC_6") (pintype "passive"))
    )
    (net (code "4") (name "+Uout") (class "Default")
      (node (ref "JP1") (pin "4") (pinfunction "4_4") (pintype "passive"))
      (node (ref "JP6") (pin "2") (pinfunction "2_2") (pintype "passive"))
      (node (ref "R56") (pin "2") (pinfunction "2_2") (pintype "passive"))
    )
    (net (code "5") (name "-5v") (class "Default")
      (node (ref "C16") (pin "2") (pinfunction "2_2") (pintype "passive"))
      (node (ref "JP6") (pin "8") (pinfunction "8_8") (pintype "passive"))
      (node (ref "Q4") (pin "3") (pinfunction "C_3") (pintype "passive"))
      (node (ref "R90") (pin "1") (pinfunction "1_1") (pintype "passive"))
    )
    (net (code "6") (name "/+5v_iz") (class "Default")
      (node (ref "JP6") (pin "10") (pinfunction "10_10") (pintype "passive"))
    )
    (net (code "7") (name "/+Iakb") (class "Default")
      (node (ref "JP1") (pin "6") (pinfunction "6_6") (pintype "passive"))
    )
    (net (code "8") (name "/-5v_iz") (class "Default")
      (node (ref "JP6") (pin "9") (pinfunction "9_9") (pintype "passive"))
    )
    (net (code "9") (name "/-Iakb") (class "Default")
      (node (ref "JP1") (pin "2") (pinfunction "2_2") (pintype "passive"))
    )
    (net (code "10") (name "/-Uout") (class "Default")
      (node (ref "JP1") (pin "21") (pinfunction "21_21") (pintype "passive"))
      (node (ref "JP6") (pin "1") (pinfunction "1_1") (pintype "passive"))
    )
    (net (code "12") (name "/C0") (class "Default")
      (node (ref "JP1") (pin "14") (pinfunction "14_14") (pintype "passive"))
    )
    (net (code "13") (name "/DT1") (class "Default")
      (node (ref "JP1") (pin "23") (pinfunction "23_23") (pintype "passive"))
      (node (ref "R17") (pin "1") (pinfunction "1_1") (pintype "passive"))
      (node (ref "R8") (pin "2") (pinfunction "2_2") (pintype "passive"))
    )
    (net (code "14") (name "/DT1u") (class "Default")
      (node (ref "C6") (pin "1") (pinfunction "1_1") (pintype "passive"))
      (node (ref "D3") (pin "2") (pinfunction "K_2") (pintype "passive"))
      (node (ref "R26") (pin "2") (pinfunction "2_2") (pintype "passive"))
      (node (ref "R8") (pin "1") (pinfunction "1_1") (pintype "passive"))
      (node (ref "U4") (pin "2") (pinfunction "X6_2") (pintype "bidirectional"))
    )
    (net (code "15") (name "/DT2") (class "Default")
      (node (ref "JP1") (pin "18") (pinfunction "18_18") (pintype "passive"))
      (node (ref "R18") (pin "1") (pinfunction "1_1") (pintype "passive"))
      (node (ref "R9") (pin "2") (pinfunction "2_2") (pintype "passive"))
    )
    (net (code "16") (name "/DT2u") (class "Default")
      (node (ref "C7") (pin "1") (pinfunction "1_1") (pintype "passive"))
      (node (ref "D4") (pin "2") (pinfunction "K_2") (pintype "passive"))
      (node (ref "R27") (pin "2") (pinfunction "2_2") (pintype "passive"))
      (node (ref "R9") (pin "1") (pinfunction "1_1") (pintype "passive"))
      (node (ref "U4") (pin "4") (pinfunction "X7_4") (pintype "bidirectional"))
    )
    (net (code "17") (name "/DTakb") (class "Default")
      (node (ref "JP1") (pin "15") (pinfunction "15_15") (pintype "passive"))
      (node (ref "R11") (pin "2") (pinfunction "2_2") (pintype "passive"))
      (node (ref "R19") (pin "1") (pinfunction "1_1") (pintype "passive"))
    )
    (net (code "18") (name "/DTakbu") (class "Default")
      (node (ref "C8") (pin "1") (pinfunction "1_1") (pintype "passive"))
      (node (ref "D5") (pin "2") (pinfunction "K_2") (pintype "passive"))
      (node (ref "R11") (pin "1") (pinfunction "1_1") (pintype "passive"))
      (node (ref "R28") (pin "2") (pinfunction "2_2") (pintype "passive"))
      (node (ref "U4") (pin "5") (pinfunction "X5_5") (pintype "bidirectional"))
    )
    (net (code "19") (name "/I1") (class "Default")
      (node (ref "JP1") (pin "13") (pinfunction "13_13") (pintype "passive"))
      (node (ref "R6") (pin "2") (pinfunction "2_2") (pintype "passive"))
    )
    (net (code "20") (name "/I2") (class "Default")
      (node (ref "JP1") (pin "7") (pinfunction "7_7") (pintype "passive"))
      (node (ref "R7") (pin "2") (pinfunction "2_2") (pintype "passive"))
    )
    (net (code "21") (name "/Iu1") (class "Default")
      (node (ref "C4") (pin "1") (pinfunction "1_1") (pintype "passive"))
      (node (ref "R23") (pin "2") (pinfunction "2_2") (pintype "passive"))
      (node (ref "R6") (pin "1") (pinfunction "1_1") (pintype "passive"))
      (node (ref "U4") (pin "12") (pinfunction "X3_12") (pintype "bidirectional"))
    )
    (net (code "22") (name "/Iu2") (class "Default")
      (node (ref "C5") (pin "1") (pinfunction "1_1") (pintype "passive"))
      (node (ref "R24") (pin "2") (pinfunction "2_2") (pintype "passive"))
      (node (ref "R7") (pin "1") (pinfunction "1_1") (pintype "passive"))
      (node (ref "U4") (pin "14") (pinfunction "X1_14") (pintype "bidirectional"))
    )
    (net (code "23") (name "/OFF1") (class "Default")
      (node (ref "JP1") (pin "19") (pinfunction "19_19") (pintype "passive"))
      (node (ref "R54") (pin "2") (pinfunction "2_2") (pintype "passive"))
    )
    (net (code "24") (name "/OFF2") (class "Default")
      (node (ref "JP1") (pin "20") (pinfunction "20_20") (pintype "passive"))
      (node (ref "R55") (pin "2") (pinfunction "2_2") (pintype "passive"))
    )
    (net (code "25") (name "/P0_0") (class "Default")
      (node (ref "U1") (pin "46") (pinfunction "P0[0]/RD1/TXD3/SDA1_46") (pintype "passive"))
    )
    (net (code "26") (name "/P0_1") (class "Default")
      (node (ref "U1") (pin "47") (pinfunction "P0[1]/TD1/RXD3/SCL1_47") (pintype "passive"))
    )
    (net (code "27") (name "/P0_2") (class "Default")
      (node (ref "U1") (pin "98") (pinfunction "P0[2]/TXD0_98") (pintype "passive"))
      (node (ref "X42") (pin "1") (pinfunction "1_1") (pintype "passive"))
    )
    (net (code "28") (name "/P0_3") (class "Default")
      (node (ref "U1") (pin "99") (pinfunction "P0[3]/RXD0_99") (pintype "passive"))
      (node (ref "X22") (pin "1") (pinfunction "1_1") (pintype "passive"))
    )
    (net (code "29") (name "/P0_4") (class "Default")
      (node (ref "U1") (pin "81") (pinfunction "P0[4]/I2SRX_CLK/RD2/CAP2[0]_81") (pintype "passive"))
    )
    (net (code "30") (name "/P0_5") (class "Default")
      (node (ref "U1") (pin "80") (pinfunction "P0[5]/I2SRX_WS/TD2/CAP2[1]_80") (pintype "passive"))
      (node (ref "U4") (pin "11") (pinfunction "A_11") (pintype "input"))
    )
    (net (code "31") (name "/P0_6") (class "Default")
      (node (ref "U1") (pin "79") (pinfunction "P0[6]/I2SRX_SDA/SSEL1/MAT2[0]_79") (pintype "passive"))
      (node (ref "U4") (pin "10") (pinfunction "B_10") (pintype "input"))
    )
    (net (code "32") (name "/P0_7") (class "Default")
      (node (ref "U1") (pin "78") (pinfunction "P0[7]/I2STX_CLK/SCK1/MAT2[1]_78") (pintype "passive"))
      (node (ref "U4") (pin "9") (pinfunction "C_9") (pintype "input"))
    )
    (net (code "33") (name "/P0_8") (class "Default")
      (node (ref "R54") (pin "1") (pinfunction "1_1") (pintype "passive"))
      (node (ref "U1") (pin "77") (pinfunction "P0[8]/I2STX_WS/MISO1/MAT2[2]_77") (pintype "passive"))
    )
    (net (code "34") (name "/P0_9") (class "Default")
      (node (ref "R55") (pin "1") (pinfunction "1_1") (pintype "passive"))
      (node (ref "U1") (pin "76") (pinfunction "P0[9]/I2STX_SDA/MOSI1/MAT2[3]_76") (pintype "passive"))
    )
    (net (code "35") (name "/P0_10") (class "Default")
      (node (ref "C42") (pin "1") (pinfunction "1_1") (pintype "passive"))
      (node (ref "D7") (pin "2") (pinfunction "K_2") (pintype "passive"))
      (node (ref "R71") (pin "2") (pinfunction "2_2") (pintype "passive"))
      (node (ref "U1") (pin "48") (pinfunction "P0[10]/TXD2/SDA2/MAT3[0]_48") (pintype "passive"))
    )
    (net (code "36") (name "/P0_11") (class "Default")
      (node (ref "U1") (pin "49") (pinfunction "P0[11]/RXD2/SCL2/MAT3[1]_49") (pintype "passive"))
    )
    (net (code "37") (name "/P0_15") (class "Default")
      (node (ref "U1") (pin "62") (pinfunction "P0[15]/TXD1/SCK0/SCK_62") (pintype "passive"))
    )
    (net (code "38") (name "/P0_16") (class "Default")
      (node (ref "U1") (pin "63") (pinfunction "P0[16]/RXD1/SSEL0/SSEL_63") (pintype "passive"))
    )
    (net (code "39") (name "/P0_17") (class "Default")
      (node (ref "U1") (pin "61") (pinfunction "P0[17]/CTS1/MISO0/MISO_61") (pintype "passive"))
    )
    (net (code "40") (name "/P0_18") (class "Default")
      (node (ref "U1") (pin "60") (pinfunction "P0[18]/DCD1/MOSI0/MOSI_60") (pintype "passive"))
    )
    (net (code "41") (name "/P0_19") (class "Default")
      (node (ref "U1") (pin "59") (pinfunction "P0[19]/DSR1/MCICLK/SDA1_59") (pintype "passive"))
    )
    (net (code "42") (name "/P0_20") (class "Default")
      (node (ref "U1") (pin "58") (pinfunction "P0[20]/DTR1/MCICMD/SCL1_58") (pintype "passive"))
    )
    (net (code "43") (name "/P0_21") (class "Default")
      (node (ref "U1") (pin "57") (pinfunction "P0[21]/RI1/MCIPWR/RD1_57") (pintype "passive"))
    )
    (net (code "44") (name "/P0_22") (class "Default")
      (node (ref "U1") (pin "56") (pinfunction "P0[22]/RTS1/MCIDAT0/TD1_56") (pintype "passive"))
    )
    (net (code "45") (name "/P0_23") (class "Default")
      (node (ref "U1") (pin "9") (pinfunction "P0[23]/AD0[0]/I2SRX_CLK/CAP3[0]_9") (pintype "passive"))
      (node (ref "U2") (pin "9") (pinfunction "R/~{W}_9") (pintype "passive"))
    )
    (net (code "46") (name "/P0_24") (class "Default")
      (node (ref "U1") (pin "8") (pinfunction "P0[24]/AD0[1]/I2SRX_WS/CAP3[1]_8") (pintype "passive"))
      (node (ref "U2") (pin "6") (pinfunction "E2_6") (pintype "passive"))
    )
    (net (code "47") (name "/P0_25") (class "Default")
      (node (ref "C3") (pin "1") (pinfunction "1_1") (pintype "passive"))
      (node (ref "R15") (pin "1") (pinfunction "1_1") (pintype "passive"))
      (node (ref "R22") (pin "1") (pinfunction "1_1") (pintype "passive"))
      (node (ref "U1") (pin "7") (pinfunction "P0[25]/AD0[2]/I2SRX_SDA/TXD3_7") (pintype "passive"))
    )
    (net (code "48") (name "/P0_26") (class "Default")
      (node (ref "R14") (pin "1") (pinfunction "1_1") (pintype "passive"))
      (node (ref "U1") (pin "6") (pinfunction "P0[26]/AD0[3]/AOUT/RXD3_6") (pintype "passive"))
    )
    (net (code "49") (name "/P0_27") (class "Default")
      (node (ref "U1") (pin "25") (pinfunction "P0[27]/SDA0_25") (pintype "passive"))
    )
    (net (code "50") (name "/P0_28") (class "Default")
      (node (ref "U1") (pin "24") (pinfunction "P0[28]/SCL0_24") (pintype "passive"))
    )
    (net (code "51") (name "/P0_29") (class "Default")
      (node (ref "U1") (pin "29") (pinfunction "P0[29]/USB_D+_29") (pintype "passive"))
      (node (ref "U2") (pin "4") (pinfunction "A0_4") (pintype "passive"))
    )
    (net (code "52") (name "/P0_30") (class "Default")
      (node (ref "U1") (pin "30") (pinfunction "P0[30]/USB_D-_30") (pintype "passive"))
      (node (ref "U2") (pin "5") (pinfunction "E1_5") (pintype "passive"))
    )
    (net (code "53") (name "/P1_0") (class "Default")
      (node (ref "U1") (pin "95") (pinfunction "P1[0]/ENET_TXD0_95") (pintype "passive"))
    )
    (net (code "54") (name "/P1_1") (class "Default")
      (node (ref "U1") (pin "94") (pinfunction "P1[1]/ENET_TXD1_94") (pintype "passive"))
    )
    (net (code "55") (name "/P1_4") (class "Default")
      (node (ref "U1") (pin "93") (pinfunction "P1[4]/ENET_TX_EN_93") (pintype "passive"))
    )
    (net (code "56") (name "/P1_8") (class "Default")
      (node (ref "U1") (pin "92") (pinfunction "P1[8]/ENET_CRS_92") (pintype "passive"))
    )
    (net (code "57") (name "/P1_9") (class "Default")
      (node (ref "U1") (pin "91") (pinfunction "P1[9]/ENET_RXD0_91") (pintype "passive"))
    )
    (net (code "58") (name "/P1_10") (class "Default")
      (node (ref "U1") (pin "90") (pinfunction "P1[10]/ENET_RXD1_90") (pintype "passive"))
    )
    (net (code "59") (name "/P1_14") (class "Default")
      (node (ref "U1") (pin "89") (pinfunction "P1[14]/ENET_RX_ER_89") (pintype "passive"))
    )
    (net (code "60") (name "/P1_15") (class "Default")
      (node (ref "U1") (pin "88") (pinfunction "P1[15]/ENET_REF_CLK_88") (pintype "passive"))
    )
    (net (code "61") (name "/P1_16") (class "Default")
      (node (ref "U1") (pin "87") (pinfunction "P1[16]/ENET_MDC_87") (pintype "passive"))
    )
    (net (code "62") (name "/P1_17") (class "Default")
      (node (ref "U1") (pin "86") (pinfunction "P1[17]/ENET_MDIO_86") (pintype "passive"))
    )
    (net (code "63") (name "/P1_18") (class "Default")
      (node (ref "U1") (pin "32") (pinfunction "P1[18]/USB_UP_LED/PWM1[1]/CAP1[0]_32") (pintype "passive"))
      (node (ref "U2") (pin "10") (pinfunction "DB0_10") (pintype "passive"))
    )
    (net (code "64") (name "/P1_19") (class "Default")
      (node (ref "U1") (pin "33") (pinfunction "P1[19]/CAP1[1]_33") (pintype "passive"))
      (node (ref "U2") (pin "11") (pinfunction "DB1_11") (pintype "passive"))
    )
    (net (code "65") (name "/P1_20") (class "Default")
      (node (ref "U1") (pin "34") (pinfunction "P1[20]/PWM1[2]/SCK0_34") (pintype "passive"))
      (node (ref "U2") (pin "12") (pinfunction "DB2_12") (pintype "passive"))
    )
    (net (code "66") (name "/P1_21") (class "Default")
      (node (ref "U1") (pin "35") (pinfunction "P1[21]/PWM1[3]/SSEL0_35") (pintype "passive"))
      (node (ref "U2") (pin "13") (pinfunction "DB3_13") (pintype "passive"))
    )
    (net (code "67") (name "/P1_22") (class "Default")
      (node (ref "U1") (pin "36") (pinfunction "P1[22]/MAT1[0]_36") (pintype "passive"))
      (node (ref "U2") (pin "14") (pinfunction "DB4_14") (pintype "passive"))
    )
    (net (code "68") (name "/P1_23") (class "Default")
      (node (ref "U1") (pin "37") (pinfunction "P1[23]/PWM1[4]/MISO0_37") (pintype "passive"))
      (node (ref "U2") (pin "15") (pinfunction "DB5_15") (pintype "passive"))
    )
    (net (code "69") (name "/P1_24") (class "Default")
      (node (ref "U1") (pin "38") (pinfunction "P1[24]/PWM1[5]/MOSI0_38") (pintype "passive"))
      (node (ref "U2") (pin "16") (pinfunction "DB6_16") (pintype "passive"))
    )
    (net (code "70") (name "/P1_25") (class "Default")
      (node (ref "U1") (pin "39") (pinfunction "P1[25]/MAT1[1]_39") (pintype "passive"))
      (node (ref "U2") (pin "17") (pinfunction "DB7_17") (pintype "passive"))
    )
    (net (code "71") (name "/P1_26") (class "Default")
      (node (ref "U1") (pin "40") (pinfunction "P1[26]/PWM1[6]/CAP0[0]_40") (pintype "passive"))
      (node (ref "U2") (pin "18") (pinfunction "RES_18") (pintype "passive"))
    )
    (net (code "72") (name "/P1_27") (class "Default")
      (node (ref "R34") (pin "1") (pinfunction "1_1") (pintype "passive"))
      (node (ref "U1") (pin "43") (pinfunction "P1[27]/CAP0[1]_43") (pintype "passive"))
    )
    (net (code "73") (name "/P1_28") (class "Default")
      (node (ref "U1") (pin "44") (pinfunction "P1[28]/PCAP1[0]/MAT0[0]_44") (pintype "passive"))
    )
    (net (code "74") (name "/P1_29") (class "Default")
      (node (ref "U1") (pin "45") (pinfunction "P1[29]/PCAP1[1]/MAT0[1]_45") (pintype "passive"))
    )
    (net (code "75") (name "/P1_30") (class "Default")
      (node (ref "R16") (pin "1") (pinfunction "1_1") (pintype "passive"))
      (node (ref "R25") (pin "1") (pinfunction "1_1") (pintype "passive"))
      (node (ref "U1") (pin "21") (pinfunction "P1[30]/VBUS/AD0[4]_21") (pintype "passive"))
    )
    (net (code "76") (name "/P1_31") (class "Default")
      (node (ref "U1") (pin "20") (pinfunction "P1[31]/SCK1/AD0[5]_20") (pintype "passive"))
      (node (ref "U4") (pin "3") (pinfunction "X_3") (pintype "bidirectional"))
    )
    (net (code "77") (name "/P2_0") (class "Default")
      (node (ref "JP2") (pin "4") (pinfunction "4_4") (pintype "passive"))
      (node (ref "U1") (pin "75") (pinfunction "P2[0]/PWM1[1]/TXD1/TRACECLK_75") (pintype "passive"))
    )
    (net (code "78") (name "/P2_1") (class "Default")
      (node (ref "JP2") (pin "5") (pinfunction "5_5") (pintype "passive"))
      (node (ref "U1") (pin "74") (pinfunction "P2[1]/PWM1[2]/RXD1/PIPESTAT0_74") (pintype "passive"))
    )
    (net (code "79") (name "/P2_2") (class "Default")
      (node (ref "JP2") (pin "3") (pinfunction "3_3") (pintype "passive"))
      (node (ref "U1") (pin "73") (pinfunction "P2[2]/PWM1[3]/CTS1/PIPESTAT1_73") (pintype "passive"))
    )
    (net (code "80") (name "/P2_3") (class "Default")
      (node (ref "JP2") (pin "2") (pinfunction "2_2") (pintype "passive"))
      (node (ref "U1") (pin "70") (pinfunction "P2[3]/PWM1[4]/DCD1/PIPESTAT2_70") (pintype "passive"))
    )
    (net (code "81") (name "/P2_4") (class "Default")
      (node (ref "JP2") (pin "1") (pinfunction "1_1") (pintype "passive"))
      (node (ref "U1") (pin "69") (pinfunction "P2[4]/PWM1[5]/DSR1/TRACESYNC_69") (pintype "passive"))
    )
    (net (code "82") (name "/P2_5") (class "Default")
      (node (ref "U1") (pin "68") (pinfunction "P2[5]/PWM1[6]/DTR1/TRACEPKT0_68") (pintype "passive"))
    )
    (net (code "83") (name "/P2_6") (class "Default")
      (node (ref "U1") (pin "67") (pinfunction "P2[6]/PCAP1[0]/RI1/TRACEPKT1_67") (pintype "passive"))
    )
    (net (code "84") (name "/P2_7") (class "Default")
      (node (ref "U1") (pin "66") (pinfunction "P2[7]/RD2/RTS1/TRACEPKT2_66") (pintype "passive"))
    )
    (net (code "85") (name "/P2_8") (class "Default")
      (node (ref "U1") (pin "65") (pinfunction "P2[8]/TD2/TXD2/TRACEPKT3_65") (pintype "passive"))
    )
    (net (code "86") (name "/P2_9") (class "Default")
      (node (ref "U1") (pin "64") (pinfunction "P2[9]/USB_CONNECT/RXD2/EXTIN0_64") (pintype "passive"))
    )
    (net (code "87") (name "/P2_10") (class "Default")
      (node (ref "U1") (pin "53") (pinfunction "P2[10]/~{EINT0}_53") (pintype "passive"))
      (node (ref "X26") (pin "1") (pinfunction "1_1") (pintype "passive"))
    )
    (net (code "88") (name "/P2_11") (class "Default")
      (node (ref "U1") (pin "52") (pinfunction "P2[11]/~{EINT1}/MCIDAT1/I2STX_CLK_52") (pintype "passive"))
    )
    (net (code "89") (name "/P2_12") (class "Default")
      (node (ref "U1") (pin "51") (pinfunction "P2[12]/~{EINT2}/MCIDAT2/I2STX_WS_51") (pintype "passive"))
    )
    (net (code "90") (name "/P2_13") (class "Default")
      (node (ref "U1") (pin "50") (pinfunction "P2[13]/~{EINT3}/MCIDAT3/I2STX_SDA_50") (pintype "passive"))
    )
    (net (code "91") (name "/P3_25") (class "Default")
      (node (ref "U1") (pin "27") (pinfunction "P3[25]/MAT0[0]/PWM1[2]_27") (pintype "passive"))
      (node (ref "U7") (pin "2") (pinfunction "inA_2") (pintype "passive"))
    )
    (net (code "92") (name "/P3_26") (class "Default")
      (node (ref "U1") (pin "26") (pinfunction "P3[26]/MAT0[1]/PWM1[3]_26") (pintype "passive"))
      (node (ref "U7") (pin "4") (pinfunction "inB_4") (pintype "passive"))
    )
    (net (code "93") (name "/P4_28") (class "Default")
      (node (ref "JP1") (pin "8") (pinfunction "8_8") (pintype "passive"))
      (node (ref "U1") (pin "82") (pinfunction "P4[28]/MAT2[0]/TXD3_82") (pintype "passive"))
    )
    (net (code "94") (name "/P4_29") (class "Default")
      (node (ref "U1") (pin "85") (pinfunction "P4[29]/MAT2[1]/RXD3_85") (pintype "passive"))
    )
    (net (code "95") (name "/PWM1") (class "Default")
      (node (ref "JP1") (pin "22") (pinfunction "22_22") (pintype "passive"))
      (node (ref "R40") (pin "1") (pinfunction "1_1") (pintype "passive"))
    )
    (net (code "96") (name "/PWM2") (class "Default")
      (node (ref "JP1") (pin "16") (pinfunction "16_16") (pintype "passive"))
      (node (ref "R41") (pin "1") (pinfunction "1_1") (pintype "passive"))
    )
    (net (code "97") (name "/RES") (class "Default")
      (node (ref "U1") (pin "17") (pinfunction "~{RESET}_17") (pintype "passive"))
      (node (ref "X34") (pin "1") (pinfunction "1_1") (pintype "passive"))
    )
    (net (code "98") (name "/RTCX1") (class "Default")
      (node (ref "C40") (pin "2") (pinfunction "2_2") (pintype "passive"))
      (node (ref "U1") (pin "16") (pinfunction "RTCX1_16") (pintype "passive"))
      (node (ref "Y2") (pin "1") (pinfunction "OSC1_1") (pintype "passive"))
    )
    (net (code "99") (name "/RTCX2") (class "Default")
      (node (ref "C41") (pin "2") (pinfunction "2_2") (pintype "passive"))
      (node (ref "U1") (pin "18") (pinfunction "RTCX2_18") (pintype "passive"))
      (node (ref "Y2") (pin "2") (pinfunction "OSC2_2") (pintype "passive"))
    )
    (net (code "100") (name "/RX0") (class "Default")
      (node (ref "X25") (pin "1") (pinfunction "1_1") (pintype "passive"))
    )
    (net (code "101") (name "/RXCAN") (class "Default")
      (node (ref "JP1") (pin "24") (pinfunction "24_24") (pintype "passive"))
    )
    (net (code "102") (name "/TX0") (class "Default")
      (node (ref "X45") (pin "1") (pinfunction "1_1") (pintype "passive"))
    )
    (net (code "103") (name "/U1") (class "Default")
      (node (ref "JP1") (pin "1") (pinfunction "1_1") (pintype "passive"))
      (node (ref "R20") (pin "2") (pinfunction "2_2") (pintype "passive"))
    )
    (net (code "104") (name "/U2") (class "Default")
      (node (ref "JP1") (pin "17") (pinfunction "17_17") (pintype "passive"))
      (node (ref "R21") (pin "2") (pinfunction "2_2") (pintype "passive"))
    )
    (net (code "105") (name "/Uakb") (class "Default")
      (node (ref "JP1") (pin "5") (pinfunction "5_5") (pintype "passive"))
      (node (ref "R22") (pin "2") (pinfunction "2_2") (pintype "passive"))
    )
    (net (code "106") (name "/Uib") (class "Default")
      (node (ref "U4") (pin "1") (pinfunction "X4_1") (pintype "bidirectional"))
    )
    (net (code "107") (name "/Us1") (class "Default")
      (node (ref "JP1") (pin "10") (pinfunction "10_10") (pintype "passive"))
      (node (ref "R25") (pin "2") (pinfunction "2_2") (pintype "passive"))
    )
    (net (code "108") (name "/Uu1") (class "Default")
      (node (ref "C1") (pin "1") (pinfunction "1_1") (pintype "passive"))
      (node (ref "R12") (pin "1") (pinfunction "1_1") (pintype "passive"))
      (node (ref "R20") (pin "1") (pinfunction "1_1") (pintype "passive"))
      (node (ref "U4") (pin "15") (pinfunction "X2_15") (pintype "bidirectional"))
    )
    (net (code "109") (name "/Uu2") (class "Default")
      (node (ref "C2") (pin "1") (pinfunction "1_1") (pintype "passive"))
      (node (ref "R13") (pin "1") (pinfunction "1_1") (pintype "passive"))
      (node (ref "R21") (pin "1") (pinfunction "1_1") (pintype "passive"))
      (node (ref "U4") (pin "13") (pinfunction "X0_13") (pintype "bidirectional"))
    )
    (net (code "110") (name "/Vbat") (class "Default")
      (node (ref "U1") (pin "19") (pinfunction "VBAT_19") (pintype "passive"))
      (node (ref "X30") (pin "1") (pinfunction "1_1") (pintype "passive"))
    )
    (net (code "111") (name "/Vs") (class "Default")
      (node (ref "JP1") (pin "25") (pinfunction "25_25") (pintype "passive"))
      (node (ref "R71") (pin "1") (pinfunction "1_1") (pintype "passive"))
    )
    (net (code "112") (name "/XTAL1") (class "Default")
      (node (ref "C21") (pin "2") (pinfunction "2_2") (pintype "passive"))
      (node (ref "U1") (pin "22") (pinfunction "XTAL1_22") (pintype "passive"))
      (node (ref "Y1") (pin "1") (pinfunction "OSC1_1") (pintype "passive"))
    )
    (net (code "113") (name "/XTAL2") (class "Default")
      (node (ref "C31") (pin "2") (pinfunction "2_2") (pintype "passive"))
      (node (ref "U1") (pin "23") (pinfunction "XTAL2_23") (pintype "passive"))
      (node (ref "Y1") (pin "2") (pinfunction "OSC2_2") (pintype "passive"))
    )
    (net (code "114") (name "/n000") (class "Default")
      (node (ref "JP9") (pin "5") (pinfunction "5_5") (pintype "passive"))
      (node (ref "JP9") (pin "8") (pinfunction "8_8") (pintype "passive"))
      (node (ref "Q7") (pin "3") (pinfunction "D_3") (pintype "passive"))
      (node (ref "X43") (pin "1") (pinfunction "1_1") (pintype "passive"))
      (node (ref "X44") (pin "1") (pinfunction "1_1") (pintype "passive"))
    )
    (net (code "115") (name "/prog_reset") (class "Default")
      (node (ref "X37") (pin "1") (pinfunction "1_1") (pintype "passive"))
    )
    (net (code "116") (name "/prog_set") (class "Default")
      (node (ref "X29") (pin "1") (pinfunction "1_1") (pintype "passive"))
    )
    (net (code "117") (name "GND") (class "Default")
      (node (ref "C1") (pin "2") (pinfunction "2_2") (pintype "passive"))
      (node (ref "C15") (pin "1") (pinfunction "1_1") (pintype "passive"))
      (node (ref "C16") (pin "1") (pinfunction "1_1") (pintype "passive"))
      (node (ref "C17") (pin "1") (pinfunction "1_1") (pintype "passive"))
      (node (ref "C19") (pin "2") (pinfunction "2_2") (pintype "passive"))
      (node (ref "C2") (pin "2") (pinfunction "2_2") (pintype "passive"))
      (node (ref "C21") (pin "1") (pinfunction "1_1") (pintype "passive"))
      (node (ref "C3") (pin "2") (pinfunction "2_2") (pintype "passive"))
      (node (ref "C31") (pin "1") (pinfunction "1_1") (pintype "passive"))
      (node (ref "C33") (pin "1") (pinfunction "1_1") (pintype "passive"))
      (node (ref "C37") (pin "1") (pinfunction "1_1") (pintype "passive"))
      (node (ref "C38") (pin "1") (pinfunction "1_1") (pintype "passive"))
      (node (ref "C39") (pin "1") (pinfunction "1_1") (pintype "passive"))
      (node (ref "C4") (pin "2") (pinfunction "2_2") (pintype "passive"))
      (node (ref "C40") (pin "1") (pinfunction "1_1") (pintype "passive"))
      (node (ref "C41") (pin "1") (pinfunction "1_1") (pintype "passive"))
      (node (ref "C42") (pin "2") (pinfunction "2_2") (pintype "passive"))
      (node (ref "C5") (pin "2") (pinfunction "2_2") (pintype "passive"))
      (node (ref "C6") (pin "2") (pinfunction "2_2") (pintype "passive"))
      (node (ref "C7") (pin "2") (pinfunction "2_2") (pintype "passive"))
      (node (ref "C8") (pin "2") (pinfunction "2_2") (pintype "passive"))
      (node (ref "D3") (pin "1") (pinfunction "A_1") (pintype "passive"))
      (node (ref "D4") (pin "1") (pinfunction "A_1") (pintype "passive"))
      (node (ref "D5") (pin "1") (pinfunction "A_1") (pintype "passive"))
      (node (ref "D7") (pin "1") (pinfunction "A_1") (pintype "passive"))
      (node (ref "JP1") (pin "12") (pinfunction "12_12") (pintype "passive"))
      (node (ref "JP1") (pin "26") (pinfunction "26_26") (pintype "passive"))
      (node (ref "JP1") (pin "3") (pinfunction "3_3") (pintype "passive"))
      (node (ref "JP4") (pin "1") (pinfunction "1_1") (pintype "passive"))
      (node (ref "JP6") (pin "7") (pinfunction "7_7") (pintype "passive"))
      (node (ref "Q1") (pin "2") (pinfunction "E_2") (pintype "passive"))
      (node (ref "Q3") (pin "2") (pinfunction "E_2") (pintype "passive"))
      (node (ref "R12") (pin "2") (pinfunction "2_2") (pintype "passive"))
      (node (ref "R13") (pin "2") (pinfunction "2_2") (pintype "passive"))
      (node (ref "R15") (pin "2") (pinfunction "2_2") (pintype "passive"))
      (node (ref "R16") (pin "2") (pinfunction "2_2") (pintype "passive"))
      (node (ref "R23") (pin "1") (pinfunction "1_1") (pintype "passive"))
      (node (ref "R24") (pin "1") (pinfunction "1_1") (pintype "passive"))
      (node (ref "R26") (pin "1") (pinfunction "1_1") (pintype "passive"))
      (node (ref "R27") (pin "1") (pinfunction "1_1") (pintype "passive"))
      (node (ref "R28") (pin "1") (pinfunction "1_1") (pintype "passive"))
      (node (ref "R36") (pin "1") (pinfunction "1_1") (pintype "passive"))
      (node (ref "R57") (pin "1") (pinfunction "1_1") (pintype "passive"))
      (node (ref "U1") (pin "11") (pinfunction "Vssa_11") (pintype "passive"))
      (node (ref "U1") (pin "15") (pinfunction "Vss_15") (pintype "passive"))
      (node (ref "U1") (pin "31") (pinfunction "Vss_31") (pintype "passive"))
      (node (ref "U1") (pin "41") (pinfunction "Vss_41") (pintype "passive"))
      (node (ref "U1") (pin "55") (pinfunction "Vss_55") (pintype "passive"))
      (node (ref "U1") (pin "72") (pinfunction "Vss_72") (pintype "passive"))
      (node (ref "U1") (pin "83") (pinfunction "Vss_83") (pintype "passive"))
      (node (ref "U1") (pin "97") (pinfunction "Vss_97") (pintype "passive"))
      (node (ref "U19") (pin "2") (pinfunction "GND_2") (pintype "power_in"))
      (node (ref "U2") (pin "1") (pinfunction "GND_1") (pintype "passive"))
      (node (ref "U2") (pin "20") (pinfunction "BL-_20") (pintype "passive"))
      (node (ref "U4") (pin "6") (pinfunction "INH_6") (pintype "input"))
      (node (ref "U4") (pin "7") (pinfunction "VEE_7") (pintype "power_in"))
      (node (ref "U4") (pin "8") (pinfunction "VSS_8") (pintype "power_in"))
      (node (ref "U7") (pin "3") (pinfunction "GND_3") (pintype "passive"))
    )
    (net (code "118") (name "Net-(A1-Pad2)") (class "Default")
      (node (ref "A1") (pin "2") (pinfunction "2_2") (pintype "passive"))
      (node (ref "C19") (pin "1") (pinfunction "1_1") (pintype "passive"))
      (node (ref "R56") (pin "1") (pinfunction "1_1") (pintype "passive"))
      (node (ref "R57") (pin "2") (pinfunction "2_2") (pintype "passive"))
    )
    (net (code "119") (name "Net-(C43-Pad2)") (class "Default")
      (node (ref "C43") (pin "2") (pinfunction "2_2") (pintype "passive"))
      (node (ref "JP8") (pin "2") (pinfunction "2_2") (pintype "passive"))
      (node (ref "JP8") (pin "3") (pinfunction "3_3") (pintype "passive"))
      (node (ref "R74") (pin "2") (pinfunction "2_2") (pintype "passive"))
    )
    (net (code "120") (name "Net-(D2-A)") (class "Default")
      (node (ref "C34") (pin "1") (pinfunction "1_1") (pintype "passive"))
      (node (ref "C43") (pin "1") (pinfunction "1_1") (pintype "passive"))
      (node (ref "C44") (pin "2") (pinfunction "2_2") (pintype "passive"))
      (node (ref "D2") (pin "1") (pinfunction "A_1") (pintype "passive"))
      (node (ref "JP5") (pin "1") (pinfunction "1_1") (pintype "passive"))
      (node (ref "JP9") (pin "1") (pinfunction "1_1") (pintype "passive"))
      (node (ref "JP9") (pin "12") (pinfunction "12_12") (pintype "passive"))
      (node (ref "Q11") (pin "2") (pinfunction "E_2") (pintype "passive"))
      (node (ref "R79") (pin "1") (pinfunction "1_1") (pintype "passive"))
      (node (ref "S1") (pin "1") (pinfunction "1_1") (pintype "passive"))
      (node (ref "S2") (pin "1") (pinfunction "1_1") (pintype "passive"))
      (node (ref "S3") (pin "1") (pinfunction "1_1") (pintype "passive"))
      (node (ref "S4") (pin "1") (pinfunction "1_1") (pintype "passive"))
      (node (ref "S5") (pin "1") (pinfunction "1_1") (pintype "passive"))
      (node (ref "S6") (pin "1") (pinfunction "1_1") (pintype "passive"))
      (node (ref "U10") (pin "2") (pinfunction "GND_2") (pintype "power_in"))
    )
    (net (code "121") (name "Net-(D2-K)") (class "Default")
      (node (ref "C36") (pin "1") (pinfunction "1_1") (pintype "passive"))
      (node (ref "D2") (pin "2") (pinfunction "K_2") (pintype "passive"))
      (node (ref "R80") (pin "2") (pinfunction "2_2") (pintype "passive"))
    )
    (net (code "122") (name "Net-(JP3-Pad1)") (class "Default")
      (node (ref "JP3") (pin "1") (pinfunction "1_1") (pintype "passive"))
      (node (ref "R1") (pin "2") (pinfunction "2_2") (pintype "passive"))
    )
    (net (code "123") (name "Net-(JP3-Pad2)") (class "Default")
      (node (ref "JP3") (pin "2") (pinfunction "2_2") (pintype "passive"))
      (node (ref "R2") (pin "2") (pinfunction "2_2") (pintype "passive"))
    )
    (net (code "124") (name "Net-(JP3-Pad3)") (class "Default")
      (node (ref "JP3") (pin "3") (pinfunction "3_3") (pintype "passive"))
      (node (ref "R3") (pin "2") (pinfunction "2_2") (pintype "passive"))
    )
    (net (code "125") (name "Net-(JP3-Pad4)") (class "Default")
      (node (ref "JP3") (pin "4") (pinfunction "4_4") (pintype "passive"))
      (node (ref "R4") (pin "2") (pinfunction "2_2") (pintype "passive"))
    )
    (net (code "126") (name "Net-(JP3-Pad5)") (class "Default")
      (node (ref "JP3") (pin "5") (pinfunction "5_5") (pintype "passive"))
      (node (ref "R5") (pin "2") (pinfunction "2_2") (pintype "passive"))
    )
    (net (code "127") (name "Net-(JP4-Pad3)") (class "Default")
      (node (ref "JP4") (pin "3") (pinfunction "3_3") (pintype "passive"))
      (node (ref "JP6") (pin "6") (pinfunction "6_6") (pintype "passive"))
    )
    (net (code "128") (name "Net-(JP5-Pad2)") (class "Default")
      (node (ref "JP5") (pin "2") (pinfunction "2_2") (pintype "passive"))
      (node (ref "X47") (pin "1") (pinfunction "1_1") (pintype "passive"))
    )
    (net (code "129") (name "Net-(JP5-Pad3)") (class "Default")
      (node (ref "JP5") (pin "3") (pinfunction "3_3") (pintype "passive"))
      (node (ref "X31") (pin "1") (pinfunction "1_1") (pintype "passive"))
    )
    (net (code "130") (name "Net-(JP9-Pad4)") (class "Default")
      (node (ref "JP9") (pin "4") (pinfunction "4_4") (pintype "passive"))
      (node (ref "JP9") (pin "9") (pinfunction "9_9") (pintype "passive"))
      (node (ref "R82") (pin "2") (pinfunction "2_2") (pintype "passive"))
      (node (ref "X27") (pin "1") (pinfunction "1_1") (pintype "passive"))
      (node (ref "X28") (pin "1") (pinfunction "1_1") (pintype "passive"))
    )
    (net (code "131") (name "Net-(JP9-Pad10)") (class "Default")
      (node (ref "JP9") (pin "10") (pinfunction "10_10") (pintype "passive"))
      (node (ref "JP9") (pin "3") (pinfunction "3_3") (pintype "passive"))
      (node (ref "R46") (pin "1") (pinfunction "1_1") (pintype "passive"))
      (node (ref "X23") (pin "1") (pinfunction "1_1") (pintype "passive"))
      (node (ref "X24") (pin "1") (pinfunction "1_1") (pintype "passive"))
    )
    (net (code "132") (name "Net-(Q1-B)") (class "Default")
      (node (ref "Q1") (pin "1") (pinfunction "B_1") (pintype "passive"))
      (node (ref "R34") (pin "2") (pinfunction "2_2") (pintype "passive"))
      (node (ref "R36") (pin "2") (pinfunction "2_2") (pintype "passive"))
    )
    (net (code "133") (name "Net-(Q1-C)") (class "Default")
      (node (ref "A1") (pin "1") (pinfunction "1_1") (pintype "passive"))
      (node (ref "Q1") (pin "3") (pinfunction "C_3") (pintype "passive"))
    )
    (net (code "134") (name "Net-(Q2-B)") (class "Default")
      (node (ref "Q2") (pin "1") (pinfunction "B_1") (pintype "passive"))
      (node (ref "R10") (pin "2") (pinfunction "2_2") (pintype "passive"))
    )
    (net (code "135") (name "Net-(Q2-C)") (class "Default")
      (node (ref "Q2") (pin "3") (pinfunction "C_3") (pintype "passive"))
      (node (ref "U2") (pin "2") (pinfunction "GND_2") (pintype "passive"))
    )
    (net (code "136") (name "Net-(Q3-B)") (class "Default")
      (node (ref "Q3") (pin "1") (pinfunction "B_1") (pintype "passive"))
      (node (ref "R14") (pin "2") (pinfunction "2_2") (pintype "passive"))
    )
    (net (code "137") (name "Net-(Q3-C)") (class "Default")
      (node (ref "Q3") (pin "3") (pinfunction "C_3") (pintype "passive"))
      (node (ref "R10") (pin "1") (pinfunction "1_1") (pintype "passive"))
    )
    (net (code "138") (name "Net-(Q4-B)") (class "Default")
      (node (ref "Q4") (pin "1") (pinfunction "B_1") (pintype "passive"))
      (node (ref "R89") (pin "1") (pinfunction "1_1") (pintype "passive"))
      (node (ref "R90") (pin "2") (pinfunction "2_2") (pintype "passive"))
    )
    (net (code "139") (name "Net-(Q4-E)") (class "Default")
      (node (ref "Q4") (pin "2") (pinfunction "E_2") (pintype "passive"))
      (node (ref "U2") (pin "3") (pinfunction "V0_3") (pintype "passive"))
    )
    (net (code "140") (name "Net-(Q7-G)") (class "Default")
      (node (ref "Q7") (pin "1") (pinfunction "G_1") (pintype "passive"))
      (node (ref "R74") (pin "1") (pinfunction "1_1") (pintype "passive"))
      (node (ref "U10") (pin "1") (pinfunction "~{RST}_1") (pintype "power_in"))
    )
    (net (code "141") (name "Net-(Q7-S)") (class "Default")
      (node (ref "Q7") (pin "2") (pinfunction "S_2") (pintype "passive"))
      (node (ref "U10") (pin "4") (pinfunction "WDI_4") (pintype "passive"))
    )
    (net (code "142") (name "Net-(Q11-B)") (class "Default")
      (node (ref "Q11") (pin "1") (pinfunction "B_1") (pintype "passive"))
      (node (ref "R79") (pin "2") (pinfunction "2_2") (pintype "passive"))
      (node (ref "R80") (pin "1") (pinfunction "1_1") (pintype "passive"))
    )
    (net (code "143") (name "Net-(Q11-C)") (class "Default")
      (node (ref "JP8") (pin "1") (pinfunction "1_1") (pintype "passive"))
      (node (ref "JP9") (pin "6") (pinfunction "6_6") (pintype "passive"))
      (node (ref "JP9") (pin "7") (pinfunction "7_7") (pintype "passive"))
      (node (ref "Q11") (pin "3") (pinfunction "C_3") (pintype "passive"))
      (node (ref "R81") (pin "2") (pinfunction "2_2") (pintype "passive"))
      (node (ref "S6") (pin "2") (pinfunction "2_2") (pintype "passive"))
      (node (ref "X35") (pin "1") (pinfunction "1_1") (pintype "passive"))
      (node (ref "X36") (pin "1") (pinfunction "1_1") (pintype "passive"))
    )
    (net (code "144") (name "Net-(R1-Pad1)") (class "Default")
      (node (ref "R1") (pin "1") (pinfunction "1_1") (pintype "passive"))
      (node (ref "S1") (pin "2") (pinfunction "2_2") (pintype "passive"))
    )
    (net (code "145") (name "Net-(R2-Pad1)") (class "Default")
      (node (ref "R2") (pin "1") (pinfunction "1_1") (pintype "passive"))
      (node (ref "S2") (pin "2") (pinfunction "2_2") (pintype "passive"))
    )
    (net (code "146") (name "Net-(R3-Pad1)") (class "Default")
      (node (ref "R3") (pin "1") (pinfunction "1_1") (pintype "passive"))
      (node (ref "S3") (pin "2") (pinfunction "2_2") (pintype "passive"))
    )
    (net (code "147") (name "Net-(R4-Pad1)") (class "Default")
      (node (ref "R4") (pin "1") (pinfunction "1_1") (pintype "passive"))
      (node (ref "S4") (pin "2") (pinfunction "2_2") (pintype "passive"))
    )
    (net (code "148") (name "Net-(R5-Pad1)") (class "Default")
      (node (ref "R5") (pin "1") (pinfunction "1_1") (pintype "passive"))
      (node (ref "S5") (pin "2") (pinfunction "2_2") (pintype "passive"))
    )
    (net (code "149") (name "Net-(U7-outA)") (class "Default")
      (node (ref "R40") (pin "2") (pinfunction "2_2") (pintype "passive"))
      (node (ref "U7") (pin "7") (pinfunction "outA_7") (pintype "passive"))
    )
    (net (code "150") (name "Net-(U7-outB)") (class "Default")
      (node (ref "R41") (pin "2") (pinfunction "2_2") (pintype "passive"))
      (node (ref "U7") (pin "5") (pinfunction "outB_5") (pintype "passive"))
    )
    (net (code "151") (name "Net-(U10-Vdd)") (class "Default")
      (node (ref "C34") (pin "2") (pinfunction "2_2") (pintype "passive"))
      (node (ref "C36") (pin "2") (pinfunction "2_2") (pintype "passive"))
      (node (ref "C44") (pin "1") (pinfunction "1_1") (pintype "passive"))
      (node (ref "JP9") (pin "11") (pinfunction "11_11") (pintype "passive"))
      (node (ref "JP9") (pin "2") (pinfunction "2_2") (pintype "passive"))
      (node (ref "R46") (pin "2") (pinfunction "2_2") (pintype "passive"))
      (node (ref "R81") (pin "1") (pinfunction "1_1") (pintype "passive"))
      (node (ref "R82") (pin "1") (pinfunction "1_1") (pintype "passive"))
      (node (ref "U10") (pin "5") (pinfunction "Vdd_5") (pintype "power_in"))
      (node (ref "X39") (pin "1") (pinfunction "1_1") (pintype "passive"))
      (node (ref "X40") (pin "1") (pinfunction "1_1") (pintype "passive"))
    )
    (net (code "152") (name "unconnected-(JP1-Pad9)") (class "Default")
      (node (ref "JP1") (pin "9") (pinfunction "9_9") (pintype "passive"))
    )
    (net (code "153") (name "unconnected-(JP4-Pad2)") (class "Default")
      (node (ref "JP4") (pin "2") (pinfunction "2_2") (pintype "passive"))
    )
    (net (code "154") (name "unconnected-(JP6-Pad4)") (class "Default")
      (node (ref "JP6") (pin "4") (pinfunction "4_4") (pintype "passive"))
    )
    (net (code "155") (name "unconnected-(U1-RTCK-Pad100)") (class "Default")
      (node (ref "U1") (pin "100") (pinfunction "RTCK_100") (pintype "passive"))
    )
    (net (code "156") (name "unconnected-(U1-TCK-Pad5)") (class "Default")
      (node (ref "U1") (pin "5") (pinfunction "TCK_5") (pintype "passive"))
    )
    (net (code "157") (name "unconnected-(U1-TDI-Pad2)") (class "Default")
      (node (ref "U1") (pin "2") (pinfunction "TDI_2") (pintype "passive"))
    )
    (net (code "158") (name "unconnected-(U1-TDO-Pad1)") (class "Default")
      (node (ref "U1") (pin "1") (pinfunction "TDO_1") (pintype "passive"))
    )
    (net (code "159") (name "unconnected-(U1-TMS-Pad3)") (class "Default")
      (node (ref "U1") (pin "3") (pinfunction "TMS_3") (pintype "passive"))
    )
    (net (code "160") (name "unconnected-(U1-~{RSTOUT}-Pad14)") (class "Default")
      (node (ref "U1") (pin "14") (pinfunction "~{RSTOUT}_14") (pintype "passive"))
    )
    (net (code "161") (name "unconnected-(U1-~{TRST}-Pad4)") (class "Default")
      (node (ref "U1") (pin "4") (pinfunction "~{TRST}_4") (pintype "passive"))
    )
    (net (code "162") (name "unconnected-(U10-~{MR}-Pad3)") (class "Default")
      (node (ref "U10") (pin "3") (pinfunction "~{MR}_3") (pintype "input"))
    )
    (net (code "163") (name "unconnected-(U19-NC-Pad4)") (class "Default")
      (node (ref "U19") (pin "4") (pinfunction "NC_4") (pintype "passive"))
    )
    (net (code "164") (name "unconnected-(X32-Pad1)") (class "Default")
      (node (ref "X32") (pin "1") (pinfunction "1_1") (pintype "passive"))
    )
    (net (code "165") (name "unconnected-(X33-Pad1)") (class "Default")
      (node (ref "X33") (pin "1") (pinfunction "1_1") (pintype "passive"))
    )
    (net (code "166") (name "unconnected-(X38-Pad1)") (class "Default")
      (node (ref "X38") (pin "1") (pinfunction "1_1") (pintype "passive"))
    )
    (net (code "167") (name "unconnected-(X46-Pad1)") (class "Default")
      (node (ref "X46") (pin "1") (pinfunction "1_1") (pintype "passive"))
    )
  )
)
